# Accelerometer.net
KiCad netlist of a schematic drawn in Altium Designer
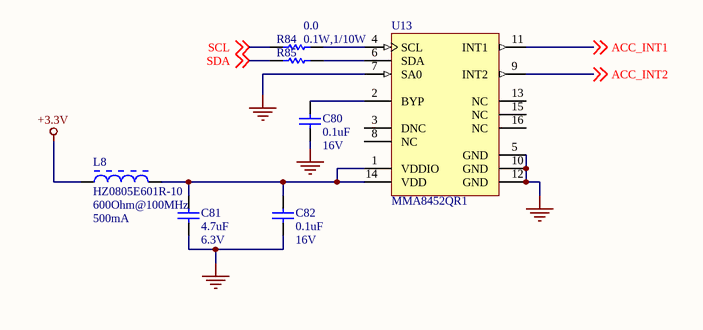
[diagram p0: Accelerometer.SchDoc]

(export (version "E")
  (design (tool "Eeschema 10.0.6"))
  (components
    (comp (ref "C80")
      (value "0.1uF")
      (footprint "CAPC1608X87X35ML15T15")
      (description "Ceramic Capacitor 0.1uF 16V +-10% X7R0603")
      (fields
        (field (name "PART NUMBER") "C0603C104M4RACTU")
        (field (name "MANUFACTURER") "Kemet")
        (field (name "VOLTAGE") "16V")
      )
      (libsource (lib "Altium Content Vault") (part "CAP"))
    )
    (comp (ref "C81")
      (value "4.7uF")
      (footprint "CAPC2013X145X50NL20T25")
      (fields
        (field (name "PART NUMBER") "C0805C475K9PACTU")
        (field (name "MANUFACTURER") "Kemet")
        (field (name "VOLTAGE") "6.3V")
      )
      (libsource (lib "Altium Content Vault") (part "CAP"))
    )
    (comp (ref "C82")
      (value "0.1uF")
      (footprint "CAPC1608X87X35ML15T15")
      (description "Ceramic Capacitor 0.1uF 16V +-10% X7R0603")
      (fields
        (field (name "PART NUMBER") "C0603C104M4RACTU")
        (field (name "MANUFACTURER") "Kemet")
        (field (name "VOLTAGE") "16V")
      )
      (libsource (lib "Altium Content Vault") (part "CAP"))
    )
    (comp (ref "L8")
      (value "HZ0805E601R-10")
      (footprint "LIRD-LI0805H151R-10-2_V")
      (fields
        (field (name "IMPEDANCE @ FREQUENCY") "600Ohm@100MHz")
        (field (name "MANUFACTURER") "Laird")
        (field (name "CURRENT RATING (MAX)") "500mA")
      )
      (libsource (lib "Altium Content Vault") (part "IND-FB-2"))
    )
    (comp (ref "R84")
      (value "0.0")
      (footprint "RESC1608X55X35LL10T10")
      (description "Chip Resistor, 0 Ohm, +/- 5%, 0.1 W, -55 to 155 degC, 0603 (1608 Metric), RoHS, Tape and Reel")
      (fields
        (field (name "POWER") "0.1W,1/10W")
        (field (name "MANUFACTURER") "Samsung-Electro-Mechanics-America,-Inc.")
        (field (name "TOLERANCE") "Jumper")
      )
      (libsource (lib "Altium Content Vault") (part "RES-2"))
    )
    (comp (ref "R85")
      (value "RC1608J000CS")
      (footprint "RESC1608X55X35LL10T10")
      (description "Chip Resistor, 0 Ohm, +/- 5%, 0.1 W, -55 to 155 degC, 0603 (1608 Metric), RoHS, Tape and Reel")
      (fields
        (field (name "POWER") "0.1W,1/10W")
        (field (name "MANUFACTURER") "Samsung-Electro-Mechanics-America,-Inc.")
      )
      (libsource (lib "Altium Content Vault") (part "RES-2"))
    )
    (comp (ref "U13")
      (value "MMA8452QR1")
      (footprint "FREE-QFN-16_V")
      (libsource (lib "Altium Content Vault") (part "FREE-MMA8452QR1-QFN-16"))
    )
  )
  (nets
    (net (code "1") (name "+3.3V") (class "Default")
      (node (ref "L8") (pin "1") (pinfunction "1_1") (pintype "passive"))
    )
    (net (code "2") (name "ACC_INT1") (class "Default")
      (node (ref "U13") (pin "11") (pinfunction "INT1_11") (pintype "output"))
    )
    (net (code "3") (name "ACC_INT2") (class "Default")
      (node (ref "U13") (pin "9") (pinfunction "INT2_9") (pintype "output"))
    )
    (net (code "4") (name "GND") (class "Default")
      (node (ref "C80") (pin "1") (pinfunction "1_1") (pintype "passive"))
      (node (ref "C81") (pin "1") (pinfunction "1_1") (pintype "passive"))
      (node (ref "C82") (pin "1") (pinfunction "1_1") (pintype "passive"))
      (node (ref "U13") (pin "10") (pinfunction "GND_10") (pintype "power_in"))
      (node (ref "U13") (pin "12") (pinfunction "GND_12") (pintype "power_in"))
      (node (ref "U13") (pin "5") (pinfunction "GND_5") (pintype "power_in"))
      (node (ref "U13") (pin "7") (pinfunction "SA0_7") (pintype "input"))
    )
    (net (code "5") (name "Net-(U13-BYP)") (class "Default")
      (node (ref "C80") (pin "2") (pinfunction "2_2") (pintype "passive"))
      (node (ref "U13") (pin "2") (pinfunction "BYP_2") (pintype "passive"))
    )
    (net (code "6") (name "Net-(U13-SCL)") (class "Default")
      (node (ref "R84") (pin "2") (pinfunction "2_2") (pintype "passive"))
      (node (ref "U13") (pin "4") (pinfunction "SCL_4") (pintype "input"))
    )
    (net (code "7") (name "Net-(U13-SDA)") (class "Default")
      (node (ref "R85") (pin "2") (pinfunction "2_2") (pintype "passive"))
      (node (ref "U13") (pin "6") (pinfunction "SDA_6") (pintype "passive"))
    )
    (net (code "8") (name "Net-(U13-VDD)") (class "Default")
      (node (ref "C81") (pin "2") (pinfunction "2_2") (pintype "passive"))
      (node (ref "C82") (pin "2") (pinfunction "2_2") (pintype "passive"))
      (node (ref "L8") (pin "2") (pinfunction "2_2") (pintype "passive"))
      (node (ref "U13") (pin "1") (pinfunction "VDDIO_1") (pintype "power_in"))
      (node (ref "U13") (pin "14") (pinfunction "VDD_14") (pintype "power_in"))
    )
    (net (code "9") (name "SCL") (class "Default")
      (node (ref "R84") (pin "1") (pinfunction "1_1") (pintype "passive"))
    )
    (net (code "10") (name "SDA") (class "Default")
      (node (ref "R85") (pin "1") (pinfunction "1_1") (pintype "passive"))
    )
    (net (code "11") (name "unconnected-(U13-DNC-Pad3)") (class "Default")
      (node (ref "U13") (pin "3") (pinfunction "DNC_3") (pintype "passive"))
    )
    (net (code "12") (name "unconnected-(U13-NC-Pad8)") (class "Default")
      (node (ref "U13") (pin "8") (pinfunction "NC_8") (pintype "passive"))
    )
    (net (code "13") (name "unconnected-(U13-NC-Pad13)") (class "Default")
      (node (ref "U13") (pin "13") (pinfunction "NC_13") (pintype "passive"))
    )
    (net (code "14") (name "unconnected-(U13-NC-Pad15)") (class "Default")
      (node (ref "U13") (pin "15") (pinfunction "NC_15") (pintype "passive"))
    )
    (net (code "15") (name "unconnected-(U13-NC-Pad16)") (class "Default")
      (node (ref "U13") (pin "16") (pinfunction "NC_16") (pintype "passive"))
    )
  )
)
